# SCH_shield_test_2024-03-16.net
KiCad netlist of a schematic drawn in EasyEDA
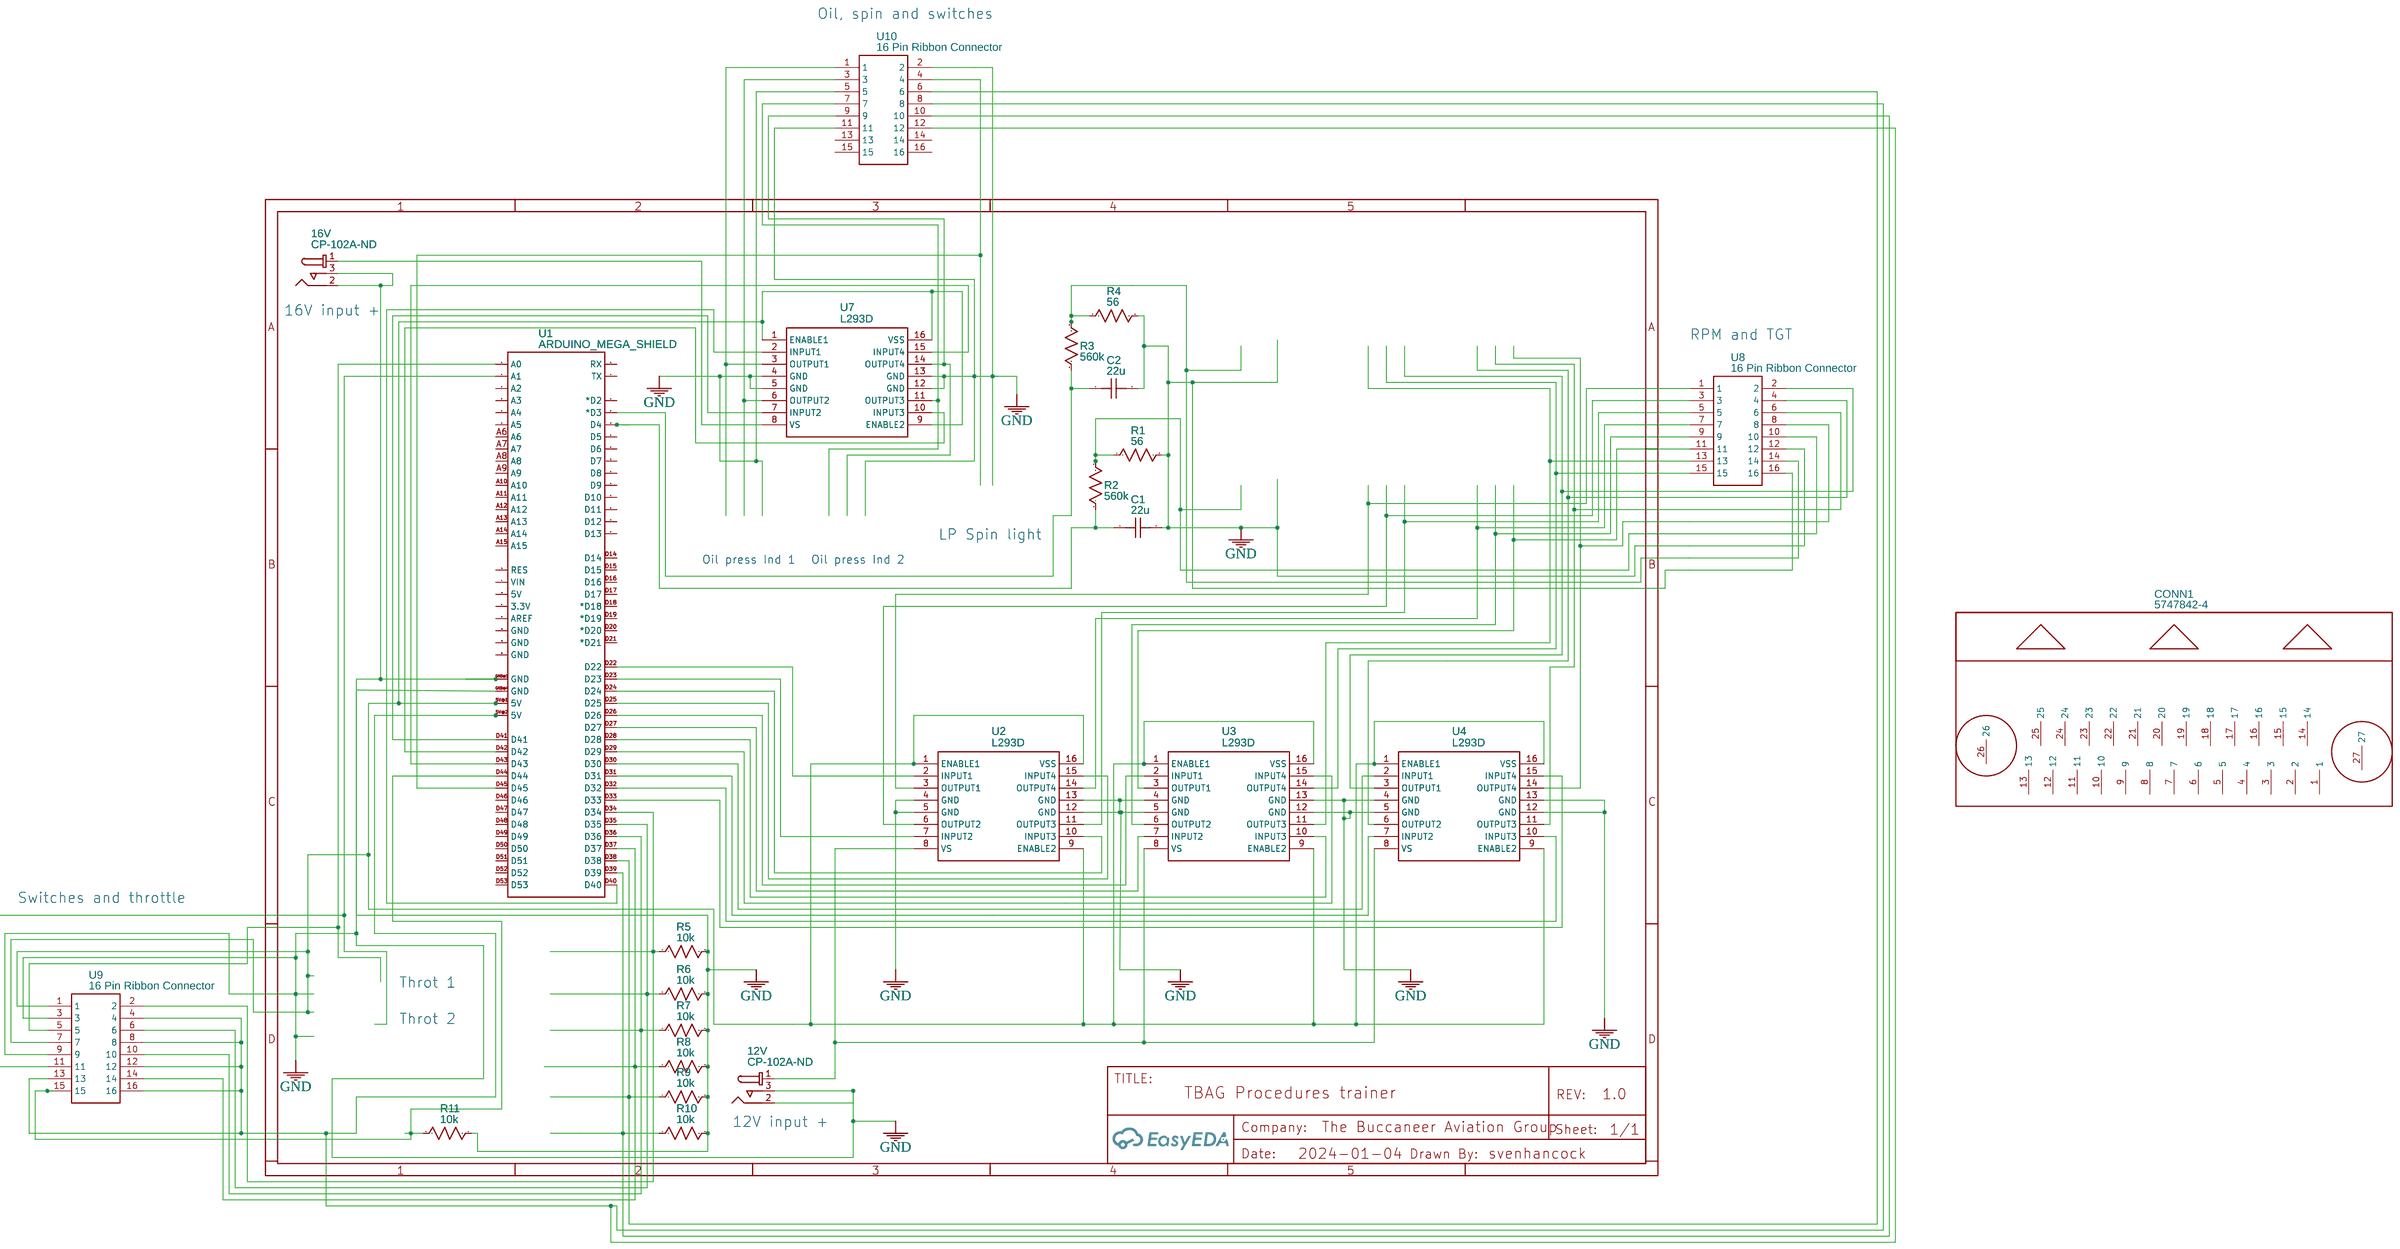
[diagram p0: schematic sheet]

(export (version "E")
  (design (tool "Eeschema 10.0.6"))
  (components
    (comp (ref "12V") (value "CP-102A-ND") (libsource (lib "") (part "CP-102A-ND_1")))
    (comp (ref "16V") (value "CP-102A-ND") (libsource (lib "") (part "CP-102A-ND")))
    (comp (ref "C1") (value "22u") (libsource (lib "") (part "C_0603_US")))
    (comp (ref "C2") (value "22u") (libsource (lib "") (part "C_0603_US")))
    (comp (ref "CONN1") (value "5747842-4") (libsource (lib "") (part "5747842-4")))
    (comp (ref "R1") (value "56") (libsource (lib "") (part "R_0603_US")))
    (comp (ref "R2") (value "560k") (libsource (lib "") (part "R_0603_US_1")))
    (comp (ref "R3") (value "560k") (libsource (lib "") (part "R_0603_US_1")))
    (comp (ref "R4") (value "56") (libsource (lib "") (part "R_0603_US")))
    (comp (ref "R5") (value "10k") (libsource (lib "") (part "R_0603_US")))
    (comp (ref "R6") (value "10k") (libsource (lib "") (part "R_0603_US")))
    (comp (ref "R7") (value "10k") (libsource (lib "") (part "R_0603_US")))
    (comp (ref "R8") (value "10k") (libsource (lib "") (part "R_0603_US")))
    (comp (ref "R9") (value "10k") (libsource (lib "") (part "R_0603_US")))
    (comp (ref "R10") (value "10k") (libsource (lib "") (part "R_0603_US")))
    (comp (ref "R11") (value "10k") (libsource (lib "") (part "R_0603_US")))
    (comp (ref "U1") (value "ARDUINO_MEGA_SHIELD") (libsource (lib "") (part "ARDUINO_MEGA_SHIELD")))
    (comp (ref "U2")
      (value "L293D")
      (fields (field (name "Manufacturer") "ST(意法半导体)"))
      (libsource (lib "") (part "L293D"))
    )
    (comp (ref "U3")
      (value "L293D")
      (fields (field (name "Manufacturer") "ST(意法半导体)"))
      (libsource (lib "") (part "L293D"))
    )
    (comp (ref "U4")
      (value "L293D")
      (fields (field (name "Manufacturer") "ST(意法半导体)"))
      (libsource (lib "") (part "L293D"))
    )
    (comp (ref "U7")
      (value "L293D")
      (fields (field (name "Manufacturer") "ST(意法半导体)"))
      (libsource (lib "") (part "L293D"))
    )
    (comp (ref "U8") (value "16 Pin Ribbon Connector") (libsource (lib "") (part "16 Pin Ribbon Connector")))
    (comp (ref "U9") (value "16 Pin Ribbon Connector") (libsource (lib "") (part "16 Pin Ribbon Connector")))
    (comp (ref "U10") (value "16 Pin Ribbon Connector") (libsource (lib "") (part "16 Pin Ribbon Connector")))
  )
  (nets
    (net (code "1") (name "GND") (class "Default")
      (node (ref "12V") (pin "2") (pintype "unspecified"))
      (node (ref "12V") (pin "3") (pintype "unspecified"))
      (node (ref "16V") (pin "2") (pintype "unspecified"))
      (node (ref "16V") (pin "3") (pintype "unspecified"))
      (node (ref "C1") (pin "2") (pinfunction "2_2") (pintype "unspecified"))
      (node (ref "C2") (pin "2") (pinfunction "2_2") (pintype "unspecified"))
      (node (ref "R1") (pin "2") (pinfunction "2_2") (pintype "unspecified"))
      (node (ref "R10") (pin "2") (pinfunction "2_2") (pintype "unspecified"))
      (node (ref "R11") (pin "2") (pinfunction "2_2") (pintype "unspecified"))
      (node (ref "R4") (pin "2") (pinfunction "2_2") (pintype "unspecified"))
      (node (ref "R5") (pin "2") (pinfunction "2_2") (pintype "unspecified"))
      (node (ref "R6") (pin "2") (pinfunction "2_2") (pintype "unspecified"))
      (node (ref "R7") (pin "2") (pinfunction "2_2") (pintype "unspecified"))
      (node (ref "R8") (pin "2") (pinfunction "2_2") (pintype "unspecified"))
      (node (ref "R9") (pin "2") (pinfunction "2_2") (pintype "unspecified"))
      (node (ref "U1") (pin "GND@3") (pinfunction "GND_GND@3") (pintype "unspecified"))
      (node (ref "U10") (pin "11") (pinfunction "11_11") (pintype "unspecified"))
      (node (ref "U10") (pin "2") (pinfunction "2_2") (pintype "unspecified"))
      (node (ref "U10") (pin "5") (pinfunction "5_5") (pintype "unspecified"))
      (node (ref "U2") (pin "12") (pinfunction "GND_12") (pintype "unspecified"))
      (node (ref "U2") (pin "13") (pinfunction "GND_13") (pintype "unspecified"))
      (node (ref "U2") (pin "4") (pinfunction "GND_4") (pintype "unspecified"))
      (node (ref "U2") (pin "5") (pinfunction "GND_5") (pintype "unspecified"))
      (node (ref "U3") (pin "12") (pinfunction "GND_12") (pintype "unspecified"))
      (node (ref "U3") (pin "13") (pinfunction "GND_13") (pintype "unspecified"))
      (node (ref "U3") (pin "4") (pinfunction "GND_4") (pintype "unspecified"))
      (node (ref "U3") (pin "5") (pinfunction "GND_5") (pintype "unspecified"))
      (node (ref "U4") (pin "12") (pinfunction "GND_12") (pintype "unspecified"))
      (node (ref "U4") (pin "13") (pinfunction "GND_13") (pintype "unspecified"))
      (node (ref "U4") (pin "4") (pinfunction "GND_4") (pintype "unspecified"))
      (node (ref "U4") (pin "5") (pinfunction "GND_5") (pintype "unspecified"))
      (node (ref "U7") (pin "12") (pinfunction "GND_12") (pintype "unspecified"))
      (node (ref "U7") (pin "13") (pinfunction "GND_13") (pintype "unspecified"))
      (node (ref "U7") (pin "4") (pinfunction "GND_4") (pintype "unspecified"))
      (node (ref "U7") (pin "5") (pinfunction "GND_5") (pintype "unspecified"))
      (node (ref "U8") (pin "12") (pinfunction "12_12") (pintype "unspecified"))
      (node (ref "U8") (pin "16") (pinfunction "16_16") (pintype "unspecified"))
      (node (ref "U9") (pin "3") (pinfunction "3_3") (pintype "unspecified"))
      (node (ref "U9") (pin "9") (pinfunction "9_9") (pintype "unspecified"))
    )
    (net (code "2") (name "Net-(C1-Pad1)") (class "Default")
      (node (ref "C1") (pin "1") (pinfunction "1_1") (pintype "unspecified"))
      (node (ref "R2") (pin "1") (pinfunction "1_1") (pintype "unspecified"))
      (node (ref "U1") (pin "D4") (pinfunction "D4_D4") (pintype "unspecified"))
    )
    (net (code "3") (name "Net-(R1-Pad1)") (class "Default")
      (node (ref "R1") (pin "1") (pinfunction "1_1") (pintype "unspecified"))
      (node (ref "R2") (pin "2") (pinfunction "2_2") (pintype "unspecified"))
      (node (ref "U8") (pin "10") (pinfunction "10_10") (pintype "unspecified"))
    )
    (net (code "4") (name "Net-(R3-Pad2)") (class "Default")
      (node (ref "R3") (pin "2") (pinfunction "2_2") (pintype "unspecified"))
      (node (ref "R4") (pin "1") (pinfunction "1_1") (pintype "unspecified"))
      (node (ref "U8") (pin "14") (pinfunction "14_14") (pintype "unspecified"))
    )
    (net (code "5") (name "Net-(R5-Pad1)") (class "Default")
      (node (ref "R5") (pin "1") (pinfunction "1_1") (pintype "unspecified"))
      (node (ref "U1") (pin "D34") (pinfunction "D34_D34") (pintype "unspecified"))
      (node (ref "U9") (pin "2") (pinfunction "2_2") (pintype "unspecified"))
    )
    (net (code "6") (name "Net-(R6-Pad1)") (class "Default")
      (node (ref "R6") (pin "1") (pinfunction "1_1") (pintype "unspecified"))
      (node (ref "U1") (pin "D35") (pinfunction "D35_D35") (pintype "unspecified"))
      (node (ref "U9") (pin "6") (pinfunction "6_6") (pintype "unspecified"))
    )
    (net (code "7") (name "Net-(R7-Pad1)") (class "Default")
      (node (ref "R7") (pin "1") (pinfunction "1_1") (pintype "unspecified"))
      (node (ref "U1") (pin "D36") (pinfunction "D36_D36") (pintype "unspecified"))
      (node (ref "U9") (pin "10") (pinfunction "10_10") (pintype "unspecified"))
    )
    (net (code "8") (name "Net-(R8-Pad1)") (class "Default")
      (node (ref "R8") (pin "1") (pinfunction "1_1") (pintype "unspecified"))
      (node (ref "U1") (pin "D37") (pinfunction "D37_D37") (pintype "unspecified"))
      (node (ref "U9") (pin "14") (pinfunction "14_14") (pintype "unspecified"))
    )
    (net (code "9") (name "Net-(R9-Pad1)") (class "Default")
      (node (ref "R9") (pin "1") (pinfunction "1_1") (pintype "unspecified"))
      (node (ref "U1") (pin "D38") (pinfunction "D38_D38") (pintype "unspecified"))
      (node (ref "U10") (pin "6") (pinfunction "6_6") (pintype "unspecified"))
    )
    (net (code "10") (name "Net-(R10-Pad1)") (class "Default")
      (node (ref "R10") (pin "1") (pinfunction "1_1") (pintype "unspecified"))
      (node (ref "U1") (pin "D39") (pinfunction "D39_D39") (pintype "unspecified"))
      (node (ref "U10") (pin "10") (pinfunction "10_10") (pintype "unspecified"))
    )
    (net (code "11") (name "Net-(R11-Pad1)") (class "Default")
      (node (ref "R11") (pin "1") (pinfunction "1_1") (pintype "unspecified"))
      (node (ref "U1") (pin "D44") (pinfunction "D44_D44") (pintype "unspecified"))
      (node (ref "U9") (pin "15") (pinfunction "15_15") (pintype "unspecified"))
    )
    (net (code "12") (name "Net-(U1-*D3)") (class "Default")
      (node (ref "C2") (pin "1") (pinfunction "1_1") (pintype "unspecified"))
      (node (ref "R3") (pin "1") (pinfunction "1_1") (pintype "unspecified"))
      (node (ref "U1") (pin "D3") (pinfunction "*D3_D3") (pintype "unspecified"))
    )
    (net (code "13") (name "Net-(U1-5V-Pad5V@2)") (class "Default")
      (node (ref "U1") (pin "5V@2") (pinfunction "5V_5V@2") (pintype "unspecified"))
      (node (ref "U10") (pin "12") (pinfunction "12_12") (pintype "unspecified"))
      (node (ref "U10") (pin "8") (pinfunction "8_8") (pintype "unspecified"))
      (node (ref "U9") (pin "12") (pinfunction "12_12") (pintype "unspecified"))
      (node (ref "U9") (pin "13") (pinfunction "13_13") (pintype "unspecified"))
      (node (ref "U9") (pin "16") (pinfunction "16_16") (pintype "unspecified"))
      (node (ref "U9") (pin "4") (pinfunction "4_4") (pintype "unspecified"))
      (node (ref "U9") (pin "8") (pinfunction "8_8") (pintype "unspecified"))
    )
    (net (code "14") (name "Net-(U1-PadA0)") (class "Default")
      (node (ref "U1") (pin "A0") (pinfunction "A0_A0") (pintype "unspecified"))
      (node (ref "U9") (pin "5") (pinfunction "5_5") (pintype "unspecified"))
    )
    (net (code "15") (name "Net-(U1-PadA1)") (class "Default")
      (node (ref "U1") (pin "A1") (pinfunction "A1_A1") (pintype "unspecified"))
      (node (ref "U9") (pin "11") (pinfunction "11_11") (pintype "unspecified"))
    )
    (net (code "16") (name "Net-(U1-PadD45)") (class "Default")
      (node (ref "U1") (pin "D45") (pinfunction "D45_D45") (pintype "unspecified"))
      (node (ref "U10") (pin "4") (pinfunction "4_4") (pintype "unspecified"))
    )
    (net (code "17") (name "Net-(U2-ENABLE1)") (class "Default")
      (node (ref "U1") (pin "5V@1") (pinfunction "5V_5V@1") (pintype "unspecified"))
      (node (ref "U2") (pin "1") (pinfunction "ENABLE1_1") (pintype "unspecified"))
      (node (ref "U2") (pin "16") (pinfunction "VSS_16") (pintype "unspecified"))
      (node (ref "U2") (pin "9") (pinfunction "ENABLE2_9") (pintype "unspecified"))
      (node (ref "U3") (pin "1") (pinfunction "ENABLE1_1") (pintype "unspecified"))
      (node (ref "U3") (pin "16") (pinfunction "VSS_16") (pintype "unspecified"))
      (node (ref "U3") (pin "9") (pinfunction "ENABLE2_9") (pintype "unspecified"))
      (node (ref "U4") (pin "1") (pinfunction "ENABLE1_1") (pintype "unspecified"))
      (node (ref "U4") (pin "16") (pinfunction "VSS_16") (pintype "unspecified"))
      (node (ref "U4") (pin "9") (pinfunction "ENABLE2_9") (pintype "unspecified"))
      (node (ref "U7") (pin "1") (pinfunction "ENABLE1_1") (pintype "unspecified"))
      (node (ref "U7") (pin "16") (pinfunction "VSS_16") (pintype "unspecified"))
      (node (ref "U7") (pin "9") (pinfunction "ENABLE2_9") (pintype "unspecified"))
      (node (ref "U9") (pin "1") (pinfunction "1_1") (pintype "unspecified"))
      (node (ref "U9") (pin "7") (pinfunction "7_7") (pintype "unspecified"))
    )
    (net (code "18") (name "Net-(U2-INPUT1)") (class "Default")
      (node (ref "U1") (pin "D22") (pinfunction "D22_D22") (pintype "unspecified"))
      (node (ref "U2") (pin "2") (pinfunction "INPUT1_2") (pintype "unspecified"))
    )
    (net (code "19") (name "Net-(U2-INPUT2)") (class "Default")
      (node (ref "U1") (pin "D23") (pinfunction "D23_D23") (pintype "unspecified"))
      (node (ref "U2") (pin "7") (pinfunction "INPUT2_7") (pintype "unspecified"))
    )
    (net (code "20") (name "Net-(U2-INPUT3)") (class "Default")
      (node (ref "U1") (pin "D24") (pinfunction "D24_D24") (pintype "unspecified"))
      (node (ref "U2") (pin "10") (pinfunction "INPUT3_10") (pintype "unspecified"))
    )
    (net (code "21") (name "Net-(U2-INPUT4)") (class "Default")
      (node (ref "U1") (pin "D25") (pinfunction "D25_D25") (pintype "unspecified"))
      (node (ref "U2") (pin "15") (pinfunction "INPUT4_15") (pintype "unspecified"))
    )
    (net (code "22") (name "Net-(U2-OUTPUT1)") (class "Default")
      (node (ref "U2") (pin "3") (pinfunction "OUTPUT1_3") (pintype "unspecified"))
      (node (ref "U8") (pin "1") (pinfunction "1_1") (pintype "unspecified"))
    )
    (net (code "23") (name "Net-(U2-OUTPUT2)") (class "Default")
      (node (ref "U2") (pin "6") (pinfunction "OUTPUT2_6") (pintype "unspecified"))
      (node (ref "U8") (pin "3") (pinfunction "3_3") (pintype "unspecified"))
    )
    (net (code "24") (name "Net-(U2-OUTPUT3)") (class "Default")
      (node (ref "U2") (pin "11") (pinfunction "OUTPUT3_11") (pintype "unspecified"))
      (node (ref "U8") (pin "5") (pinfunction "5_5") (pintype "unspecified"))
    )
    (net (code "25") (name "Net-(U2-OUTPUT4)") (class "Default")
      (node (ref "U2") (pin "14") (pinfunction "OUTPUT4_14") (pintype "unspecified"))
      (node (ref "U8") (pin "7") (pinfunction "7_7") (pintype "unspecified"))
    )
    (net (code "26") (name "Net-(U2-VS)") (class "Default")
      (node (ref "12V") (pin "1") (pintype "unspecified"))
      (node (ref "U2") (pin "8") (pinfunction "VS_8") (pintype "unspecified"))
      (node (ref "U3") (pin "8") (pinfunction "VS_8") (pintype "unspecified"))
      (node (ref "U4") (pin "8") (pinfunction "VS_8") (pintype "unspecified"))
    )
    (net (code "27") (name "Net-(U3-INPUT1)") (class "Default")
      (node (ref "U1") (pin "D26") (pinfunction "D26_D26") (pintype "unspecified"))
      (node (ref "U3") (pin "2") (pinfunction "INPUT1_2") (pintype "unspecified"))
    )
    (net (code "28") (name "Net-(U3-INPUT2)") (class "Default")
      (node (ref "U1") (pin "D27") (pinfunction "D27_D27") (pintype "unspecified"))
      (node (ref "U3") (pin "7") (pinfunction "INPUT2_7") (pintype "unspecified"))
    )
    (net (code "29") (name "Net-(U3-INPUT3)") (class "Default")
      (node (ref "U1") (pin "D28") (pinfunction "D28_D28") (pintype "unspecified"))
      (node (ref "U3") (pin "10") (pinfunction "INPUT3_10") (pintype "unspecified"))
    )
    (net (code "30") (name "Net-(U3-INPUT4)") (class "Default")
      (node (ref "U1") (pin "D29") (pinfunction "D29_D29") (pintype "unspecified"))
      (node (ref "U3") (pin "15") (pinfunction "INPUT4_15") (pintype "unspecified"))
    )
    (net (code "31") (name "Net-(U3-OUTPUT1)") (class "Default")
      (node (ref "U3") (pin "3") (pinfunction "OUTPUT1_3") (pintype "unspecified"))
      (node (ref "U8") (pin "11") (pinfunction "11_11") (pintype "unspecified"))
    )
    (net (code "32") (name "Net-(U3-OUTPUT2)") (class "Default")
      (node (ref "U3") (pin "6") (pinfunction "OUTPUT2_6") (pintype "unspecified"))
      (node (ref "U8") (pin "9") (pinfunction "9_9") (pintype "unspecified"))
    )
    (net (code "33") (name "Net-(U3-OUTPUT3)") (class "Default")
      (node (ref "U3") (pin "11") (pinfunction "OUTPUT3_11") (pintype "unspecified"))
      (node (ref "U8") (pin "13") (pinfunction "13_13") (pintype "unspecified"))
    )
    (net (code "34") (name "Net-(U3-OUTPUT4)") (class "Default")
      (node (ref "U3") (pin "14") (pinfunction "OUTPUT4_14") (pintype "unspecified"))
      (node (ref "U8") (pin "15") (pinfunction "15_15") (pintype "unspecified"))
    )
    (net (code "35") (name "Net-(U4-INPUT1)") (class "Default")
      (node (ref "U1") (pin "D30") (pinfunction "D30_D30") (pintype "unspecified"))
      (node (ref "U4") (pin "2") (pinfunction "INPUT1_2") (pintype "unspecified"))
    )
    (net (code "36") (name "Net-(U4-INPUT2)") (class "Default")
      (node (ref "U1") (pin "D31") (pinfunction "D31_D31") (pintype "unspecified"))
      (node (ref "U4") (pin "7") (pinfunction "INPUT2_7") (pintype "unspecified"))
    )
    (net (code "37") (name "Net-(U4-INPUT3)") (class "Default")
      (node (ref "U1") (pin "D32") (pinfunction "D32_D32") (pintype "unspecified"))
      (node (ref "U4") (pin "10") (pinfunction "INPUT3_10") (pintype "unspecified"))
    )
    (net (code "38") (name "Net-(U4-INPUT4)") (class "Default")
      (node (ref "U1") (pin "D33") (pinfunction "D33_D33") (pintype "unspecified"))
      (node (ref "U4") (pin "15") (pinfunction "INPUT4_15") (pintype "unspecified"))
    )
    (net (code "39") (name "Net-(U4-OUTPUT1)") (class "Default")
      (node (ref "U4") (pin "3") (pinfunction "OUTPUT1_3") (pintype "unspecified"))
      (node (ref "U8") (pin "2") (pinfunction "2_2") (pintype "unspecified"))
    )
    (net (code "40") (name "Net-(U4-OUTPUT2)") (class "Default")
      (node (ref "U4") (pin "6") (pinfunction "OUTPUT2_6") (pintype "unspecified"))
      (node (ref "U8") (pin "4") (pinfunction "4_4") (pintype "unspecified"))
    )
    (net (code "41") (name "Net-(U4-OUTPUT3)") (class "Default")
      (node (ref "U4") (pin "11") (pinfunction "OUTPUT3_11") (pintype "unspecified"))
      (node (ref "U8") (pin "6") (pinfunction "6_6") (pintype "unspecified"))
    )
    (net (code "42") (name "Net-(U4-OUTPUT4)") (class "Default")
      (node (ref "U4") (pin "14") (pinfunction "OUTPUT4_14") (pintype "unspecified"))
      (node (ref "U8") (pin "8") (pinfunction "8_8") (pintype "unspecified"))
    )
    (net (code "43") (name "Net-(U7-INPUT1)") (class "Default")
      (node (ref "U1") (pin "D40") (pinfunction "D40_D40") (pintype "unspecified"))
      (node (ref "U7") (pin "2") (pinfunction "INPUT1_2") (pintype "unspecified"))
    )
    (net (code "44") (name "Net-(U7-INPUT2)") (class "Default")
      (node (ref "U1") (pin "D41") (pinfunction "D41_D41") (pintype "unspecified"))
      (node (ref "U7") (pin "7") (pinfunction "INPUT2_7") (pintype "unspecified"))
    )
    (net (code "45") (name "Net-(U7-INPUT3)") (class "Default")
      (node (ref "U1") (pin "D42") (pinfunction "D42_D42") (pintype "unspecified"))
      (node (ref "U7") (pin "10") (pinfunction "INPUT3_10") (pintype "unspecified"))
    )
    (net (code "46") (name "Net-(U7-INPUT4)") (class "Default")
      (node (ref "U1") (pin "D43") (pinfunction "D43_D43") (pintype "unspecified"))
      (node (ref "U7") (pin "15") (pinfunction "INPUT4_15") (pintype "unspecified"))
    )
    (net (code "47") (name "Net-(U7-OUTPUT1)") (class "Default")
      (node (ref "U10") (pin "1") (pinfunction "1_1") (pintype "unspecified"))
      (node (ref "U7") (pin "3") (pinfunction "OUTPUT1_3") (pintype "unspecified"))
    )
    (net (code "48") (name "Net-(U7-OUTPUT2)") (class "Default")
      (node (ref "U10") (pin "3") (pinfunction "3_3") (pintype "unspecified"))
      (node (ref "U7") (pin "6") (pinfunction "OUTPUT2_6") (pintype "unspecified"))
    )
    (net (code "49") (name "Net-(U7-OUTPUT3)") (class "Default")
      (node (ref "U10") (pin "7") (pinfunction "7_7") (pintype "unspecified"))
      (node (ref "U7") (pin "11") (pinfunction "OUTPUT3_11") (pintype "unspecified"))
    )
    (net (code "50") (name "Net-(U7-OUTPUT4)") (class "Default")
      (node (ref "U10") (pin "9") (pinfunction "9_9") (pintype "unspecified"))
      (node (ref "U7") (pin "14") (pinfunction "OUTPUT4_14") (pintype "unspecified"))
    )
    (net (code "51") (name "Net-(U7-VS)") (class "Default")
      (node (ref "16V") (pin "1") (pintype "unspecified"))
      (node (ref "U7") (pin "8") (pinfunction "VS_8") (pintype "unspecified"))
    )
    (net (code "52") (name "unconnected-(CONN1-Pad1)") (class "Default")
      (node (ref "CONN1") (pin "1") (pinfunction "1_1") (pintype "unspecified"))
    )
    (net (code "53") (name "unconnected-(CONN1-Pad2)") (class "Default")
      (node (ref "CONN1") (pin "2") (pinfunction "2_2") (pintype "unspecified"))
    )
    (net (code "54") (name "unconnected-(CONN1-Pad3)") (class "Default")
      (node (ref "CONN1") (pin "3") (pinfunction "3_3") (pintype "unspecified"))
    )
    (net (code "55") (name "unconnected-(CONN1-Pad4)") (class "Default")
      (node (ref "CONN1") (pin "4") (pinfunction "4_4") (pintype "unspecified"))
    )
    (net (code "56") (name "unconnected-(CONN1-Pad5)") (class "Default")
      (node (ref "CONN1") (pin "5") (pinfunction "5_5") (pintype "unspecified"))
    )
    (net (code "57") (name "unconnected-(CONN1-Pad6)") (class "Default")
      (node (ref "CONN1") (pin "6") (pinfunction "6_6") (pintype "unspecified"))
    )
    (net (code "58") (name "unconnected-(CONN1-Pad7)") (class "Default")
      (node (ref "CONN1") (pin "7") (pinfunction "7_7") (pintype "unspecified"))
    )
    (net (code "59") (name "unconnected-(CONN1-Pad8)") (class "Default")
      (node (ref "CONN1") (pin "8") (pinfunction "8_8") (pintype "unspecified"))
    )
    (net (code "60") (name "unconnected-(CONN1-Pad9)") (class "Default")
      (node (ref "CONN1") (pin "9") (pinfunction "9_9") (pintype "unspecified"))
    )
    (net (code "61") (name "unconnected-(CONN1-Pad10)") (class "Default")
      (node (ref "CONN1") (pin "10") (pinfunction "10_10") (pintype "unspecified"))
    )
    (net (code "62") (name "unconnected-(CONN1-Pad11)") (class "Default")
      (node (ref "CONN1") (pin "11") (pinfunction "11_11") (pintype "unspecified"))
    )
    (net (code "63") (name "unconnected-(CONN1-Pad12)") (class "Default")
      (node (ref "CONN1") (pin "12") (pinfunction "12_12") (pintype "unspecified"))
    )
    (net (code "64") (name "unconnected-(CONN1-Pad13)") (class "Default")
      (node (ref "CONN1") (pin "13") (pinfunction "13_13") (pintype "unspecified"))
    )
    (net (code "65") (name "unconnected-(CONN1-Pad14)") (class "Default")
      (node (ref "CONN1") (pin "14") (pinfunction "14_14") (pintype "unspecified"))
    )
    (net (code "66") (name "unconnected-(CONN1-Pad15)") (class "Default")
      (node (ref "CONN1") (pin "15") (pinfunction "15_15") (pintype "unspecified"))
    )
    (net (code "67") (name "unconnected-(CONN1-Pad16)") (class "Default")
      (node (ref "CONN1") (pin "16") (pinfunction "16_16") (pintype "unspecified"))
    )
    (net (code "68") (name "unconnected-(CONN1-Pad17)") (class "Default")
      (node (ref "CONN1") (pin "17") (pinfunction "17_17") (pintype "unspecified"))
    )
    (net (code "69") (name "unconnected-(CONN1-Pad18)") (class "Default")
      (node (ref "CONN1") (pin "18") (pinfunction "18_18") (pintype "unspecified"))
    )
    (net (code "70") (name "unconnected-(CONN1-Pad19)") (class "Default")
      (node (ref "CONN1") (pin "19") (pinfunction "19_19") (pintype "unspecified"))
    )
    (net (code "71") (name "unconnected-(CONN1-Pad20)") (class "Default")
      (node (ref "CONN1") (pin "20") (pinfunction "20_20") (pintype "unspecified"))
    )
    (net (code "72") (name "unconnected-(CONN1-Pad21)") (class "Default")
      (node (ref "CONN1") (pin "21") (pinfunction "21_21") (pintype "unspecified"))
    )
    (net (code "73") (name "unconnected-(CONN1-Pad22)") (class "Default")
      (node (ref "CONN1") (pin "22") (pinfunction "22_22") (pintype "unspecified"))
    )
    (net (code "74") (name "unconnected-(CONN1-Pad23)") (class "Default")
      (node (ref "CONN1") (pin "23") (pinfunction "23_23") (pintype "unspecified"))
    )
    (net (code "75") (name "unconnected-(CONN1-Pad24)") (class "Default")
      (node (ref "CONN1") (pin "24") (pinfunction "24_24") (pintype "unspecified"))
    )
    (net (code "76") (name "unconnected-(CONN1-Pad25)") (class "Default")
      (node (ref "CONN1") (pin "25") (pinfunction "25_25") (pintype "unspecified"))
    )
    (net (code "77") (name "unconnected-(CONN1-Pad26)") (class "Default")
      (node (ref "CONN1") (pin "26") (pinfunction "26_26") (pintype "unspecified"))
    )
    (net (code "78") (name "unconnected-(CONN1-Pad27)") (class "Default")
      (node (ref "CONN1") (pin "27") (pinfunction "27_27") (pintype "unspecified"))
    )
    (net (code "79") (name "unconnected-(U1-*D2-PadD2)") (class "Default")
      (node (ref "U1") (pin "D2") (pinfunction "*D2_D2") (pintype "unspecified"))
    )
    (net (code "80") (name "unconnected-(U1-*D18-PadD18)") (class "Default")
      (node (ref "U1") (pin "D18") (pinfunction "*D18_D18") (pintype "unspecified"))
    )
    (net (code "81") (name "unconnected-(U1-*D19-PadD19)") (class "Default")
      (node (ref "U1") (pin "D19") (pinfunction "*D19_D19") (pintype "unspecified"))
    )
    (net (code "82") (name "unconnected-(U1-*D20-PadD20)") (class "Default")
      (node (ref "U1") (pin "D20") (pinfunction "*D20_D20") (pintype "unspecified"))
    )
    (net (code "83") (name "unconnected-(U1-*D21-PadD21)") (class "Default")
      (node (ref "U1") (pin "D21") (pinfunction "*D21_D21") (pintype "unspecified"))
    )
    (net (code "84") (name "unconnected-(U1-5V-Pad5V@0)") (class "Default")
      (node (ref "U1") (pin "5V@0") (pinfunction "5V_5V@0") (pintype "passive"))
    )
    (net (code "85") (name "unconnected-(U1-GND-PadGND@0)") (class "Default")
      (node (ref "U1") (pin "GND@0") (pinfunction "GND_GND@0") (pintype "unspecified"))
    )
    (net (code "86") (name "unconnected-(U1-GND-PadGND@1)") (class "Default")
      (node (ref "U1") (pin "GND@1") (pinfunction "GND_GND@1") (pintype "unspecified"))
    )
    (net (code "87") (name "unconnected-(U1-GND-PadGND@2)") (class "Default")
      (node (ref "U1") (pin "GND@2") (pinfunction "GND_GND@2") (pintype "unspecified"))
    )
    (net (code "88") (name "unconnected-(U1-GND-PadGND@4)") (class "Default")
      (node (ref "U1") (pin "GND@4") (pinfunction "GND_GND@4") (pintype "unspecified"))
    )
    (net (code "89") (name "unconnected-(U1-Pad3.3V)") (class "Default")
      (node (ref "U1") (pin "3.3V") (pinfunction "3.3V_3.3V") (pintype "unspecified"))
    )
    (net (code "90") (name "unconnected-(U1-PadA2)") (class "Default")
      (node (ref "U1") (pin "A2") (pinfunction "A2_A2") (pintype "unspecified"))
    )
    (net (code "91") (name "unconnected-(U1-PadA3)") (class "Default")
      (node (ref "U1") (pin "A3") (pinfunction "A3_A3") (pintype "unspecified"))
    )
    (net (code "92") (name "unconnected-(U1-PadA4)") (class "Default")
      (node (ref "U1") (pin "A4") (pinfunction "A4_A4") (pintype "unspecified"))
    )
    (net (code "93") (name "unconnected-(U1-PadA5)") (class "Default")
      (node (ref "U1") (pin "A5") (pinfunction "A5_A5") (pintype "unspecified"))
    )
    (net (code "94") (name "unconnected-(U1-PadA6)") (class "Default")
      (node (ref "U1") (pin "A6") (pinfunction "A6_A6") (pintype "unspecified"))
    )
    (net (code "95") (name "unconnected-(U1-PadA7)") (class "Default")
      (node (ref "U1") (pin "A7") (pinfunction "A7_A7") (pintype "unspecified"))
    )
    (net (code "96") (name "unconnected-(U1-PadA8)") (class "Default")
      (node (ref "U1") (pin "A8") (pinfunction "A8_A8") (pintype "unspecified"))
    )
    (net (code "97") (name "unconnected-(U1-PadA9)") (class "Default")
      (node (ref "U1") (pin "A9") (pinfunction "A9_A9") (pintype "unspecified"))
    )
    (net (code "98") (name "unconnected-(U1-PadA10)") (class "Default")
      (node (ref "U1") (pin "A10") (pinfunction "A10_A10") (pintype "unspecified"))
    )
    (net (code "99") (name "unconnected-(U1-PadA11)") (class "Default")
      (node (ref "U1") (pin "A11") (pinfunction "A11_A11") (pintype "unspecified"))
    )
    (net (code "100") (name "unconnected-(U1-PadA12)") (class "Default")
      (node (ref "U1") (pin "A12") (pinfunction "A12_A12") (pintype "unspecified"))
    )
    (net (code "101") (name "unconnected-(U1-PadA13)") (class "Default")
      (node (ref "U1") (pin "A13") (pinfunction "A13_A13") (pintype "unspecified"))
    )
    (net (code "102") (name "unconnected-(U1-PadA14)") (class "Default")
      (node (ref "U1") (pin "A14") (pinfunction "A14_A14") (pintype "unspecified"))
    )
    (net (code "103") (name "unconnected-(U1-PadA15)") (class "Default")
      (node (ref "U1") (pin "A15") (pinfunction "A15_A15") (pintype "unspecified"))
    )
    (net (code "104") (name "unconnected-(U1-PadAREF)") (class "Default")
      (node (ref "U1") (pin "AREF") (pinfunction "AREF_AREF") (pintype "unspecified"))
    )
    (net (code "105") (name "unconnected-(U1-PadD5)") (class "Default")
      (node (ref "U1") (pin "D5") (pinfunction "D5_D5") (pintype "unspecified"))
    )
    (net (code "106") (name "unconnected-(U1-PadD6)") (class "Default")
      (node (ref "U1") (pin "D6") (pinfunction "D6_D6") (pintype "unspecified"))
    )
    (net (code "107") (name "unconnected-(U1-PadD7)") (class "Default")
      (node (ref "U1") (pin "D7") (pinfunction "D7_D7") (pintype "unspecified"))
    )
    (net (code "108") (name "unconnected-(U1-PadD8)") (class "Default")
      (node (ref "U1") (pin "D8") (pinfunction "D8_D8") (pintype "unspecified"))
    )
    (net (code "109") (name "unconnected-(U1-PadD9)") (class "Default")
      (node (ref "U1") (pin "D9") (pinfunction "D9_D9") (pintype "unspecified"))
    )
    (net (code "110") (name "unconnected-(U1-PadD10)") (class "Default")
      (node (ref "U1") (pin "D10") (pinfunction "D10_D10") (pintype "unspecified"))
    )
    (net (code "111") (name "unconnected-(U1-PadD11)") (class "Default")
      (node (ref "U1") (pin "D11") (pinfunction "D11_D11") (pintype "unspecified"))
    )
    (net (code "112") (name "unconnected-(U1-PadD12)") (class "Default")
      (node (ref "U1") (pin "D12") (pinfunction "D12_D12") (pintype "unspecified"))
    )
    (net (code "113") (name "unconnected-(U1-PadD13)") (class "Default")
      (node (ref "U1") (pin "D13") (pinfunction "D13_D13") (pintype "unspecified"))
    )
    (net (code "114") (name "unconnected-(U1-PadD14)") (class "Default")
      (node (ref "U1") (pin "D14") (pinfunction "D14_D14") (pintype "unspecified"))
    )
    (net (code "115") (name "unconnected-(U1-PadD15)") (class "Default")
      (node (ref "U1") (pin "D15") (pinfunction "D15_D15") (pintype "unspecified"))
    )
    (net (code "116") (name "unconnected-(U1-PadD16)") (class "Default")
      (node (ref "U1") (pin "D16") (pinfunction "D16_D16") (pintype "unspecified"))
    )
    (net (code "117") (name "unconnected-(U1-PadD17)") (class "Default")
      (node (ref "U1") (pin "D17") (pinfunction "D17_D17") (pintype "unspecified"))
    )
    (net (code "118") (name "unconnected-(U1-PadD46)") (class "Default")
      (node (ref "U1") (pin "D46") (pinfunction "D46_D46") (pintype "unspecified"))
    )
    (net (code "119") (name "unconnected-(U1-PadD47)") (class "Default")
      (node (ref "U1") (pin "D47") (pinfunction "D47_D47") (pintype "unspecified"))
    )
    (net (code "120") (name "unconnected-(U1-PadD48)") (class "Default")
      (node (ref "U1") (pin "D48") (pinfunction "D48_D48") (pintype "unspecified"))
    )
    (net (code "121") (name "unconnected-(U1-PadD49)") (class "Default")
      (node (ref "U1") (pin "D49") (pinfunction "D49_D49") (pintype "unspecified"))
    )
    (net (code "122") (name "unconnected-(U1-PadD50)") (class "Default")
      (node (ref "U1") (pin "D50") (pinfunction "D50_D50") (pintype "unspecified"))
    )
    (net (code "123") (name "unconnected-(U1-PadD51)") (class "Default")
      (node (ref "U1") (pin "D51") (pinfunction "D51_D51") (pintype "unspecified"))
    )
    (net (code "124") (name "unconnected-(U1-PadD52)") (class "Default")
      (node (ref "U1") (pin "D52") (pinfunction "D52_D52") (pintype "unspecified"))
    )
    (net (code "125") (name "unconnected-(U1-PadD53)") (class "Default")
      (node (ref "U1") (pin "D53") (pinfunction "D53_D53") (pintype "unspecified"))
    )
    (net (code "126") (name "unconnected-(U1-PadRES)") (class "Default")
      (node (ref "U1") (pin "RES") (pinfunction "RES_RES") (pintype "unspecified"))
    )
    (net (code "127") (name "unconnected-(U1-PadRX)") (class "Default")
      (node (ref "U1") (pin "RX") (pinfunction "RX_RX") (pintype "unspecified"))
    )
    (net (code "128") (name "unconnected-(U1-PadTX)") (class "Default")
      (node (ref "U1") (pin "TX") (pinfunction "TX_TX") (pintype "unspecified"))
    )
    (net (code "129") (name "unconnected-(U1-PadVIN)") (class "Default")
      (node (ref "U1") (pin "VIN") (pinfunction "VIN_VIN") (pintype "unspecified"))
    )
    (net (code "130") (name "unconnected-(U10-Pad13)") (class "Default")
      (node (ref "U10") (pin "13") (pinfunction "13_13") (pintype "unspecified"))
    )
    (net (code "131") (name "unconnected-(U10-Pad14)") (class "Default")
      (node (ref "U10") (pin "14") (pinfunction "14_14") (pintype "unspecified"))
    )
    (net (code "132") (name "unconnected-(U10-Pad15)") (class "Default")
      (node (ref "U10") (pin "15") (pinfunction "15_15") (pintype "unspecified"))
    )
    (net (code "133") (name "unconnected-(U10-Pad16)") (class "Default")
      (node (ref "U10") (pin "16") (pinfunction "16_16") (pintype "unspecified"))
    )
  )
)
